# LC_LPF14.net
KiCad netlist of a schematic drawn in Altium Designer
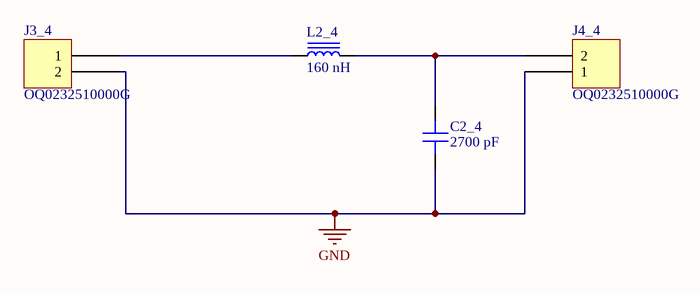
[diagram p0: LC_LPF14.SchDoc]

(export (version "E")
  (design (tool "Eeschema 10.0.6"))
  (components
    (comp (ref "C2_4")
      (value "2700 pF")
      (footprint "CAP 0603_1608")
      (description "CAP CER 2700PF 25V NP0 0603")
      (fields (field (name "PART NUMBER") "C0603C272F3GAC7867") (field (name "MANUFACTURER") "KEMET"))
      (libsource (lib "Celestial Altium Library - altium_library") (part "Capacitor"))
    )
    (comp (ref "J3_4")
      (value "OQ0232510000G")
      (footprint "FCI 06-381-2PIN")
      (description "TERM BLOCK HDR 2POS 90DEG 3.81MM")
      (fields (field (name "MANUFACTURER") "Amphenol Anytek"))
      (libsource (lib "") (part "2 Pin_1"))
    )
    (comp (ref "J4_4")
      (value "OQ0232510000G")
      (footprint "FCI 06-381-2PIN")
      (description "TERM BLOCK HDR 2POS 90DEG 3.81MM")
      (fields (field (name "MANUFACTURER") "Amphenol Anytek"))
      (libsource (lib "Celestial Altium Library - altium_library") (part "2 Pin"))
    )
    (comp (ref "L2_4")
      (value "160 nH")
      (footprint "IND 0402_1005 RF WW")
      (description "FIXED IND 160NH 480MA 330MOHM SM")
      (fields
        (field (name "PART NUMBER") "LQW15CNR16J00D")
        (field (name "MANUFACTURER") "Murata Electronics")
      )
      (libsource (lib "Celestial Altium Library - altium_library") (part "Inductor"))
    )
  )
  (nets
    (net (code "1") (name "GND") (class "Default")
      (node (ref "C2_4") (pin "1") (pinfunction "1_1") (pintype "passive"))
      (node (ref "J3_4") (pin "2") (pinfunction "2_2") (pintype "passive"))
      (node (ref "J4_4") (pin "1") (pinfunction "1_1") (pintype "passive"))
    )
    (net (code "2") (name "Net-(C2_4-Pad2)") (class "Default")
      (node (ref "C2_4") (pin "2") (pinfunction "2_2") (pintype "passive"))
      (node (ref "J4_4") (pin "2") (pinfunction "2_2") (pintype "passive"))
      (node (ref "L2_4") (pin "2") (pinfunction "2_2") (pintype "passive"))
    )
    (net (code "3") (name "Net-(J3_4-Pad1)") (class "Default")
      (node (ref "J3_4") (pin "1") (pinfunction "1_1") (pintype "passive"))
      (node (ref "L2_4") (pin "1") (pinfunction "1_1") (pintype "passive"))
    )
  )
)
